# ArbPwrBoost_P7.net
KiCad netlist of a schematic drawn in Altium Designer
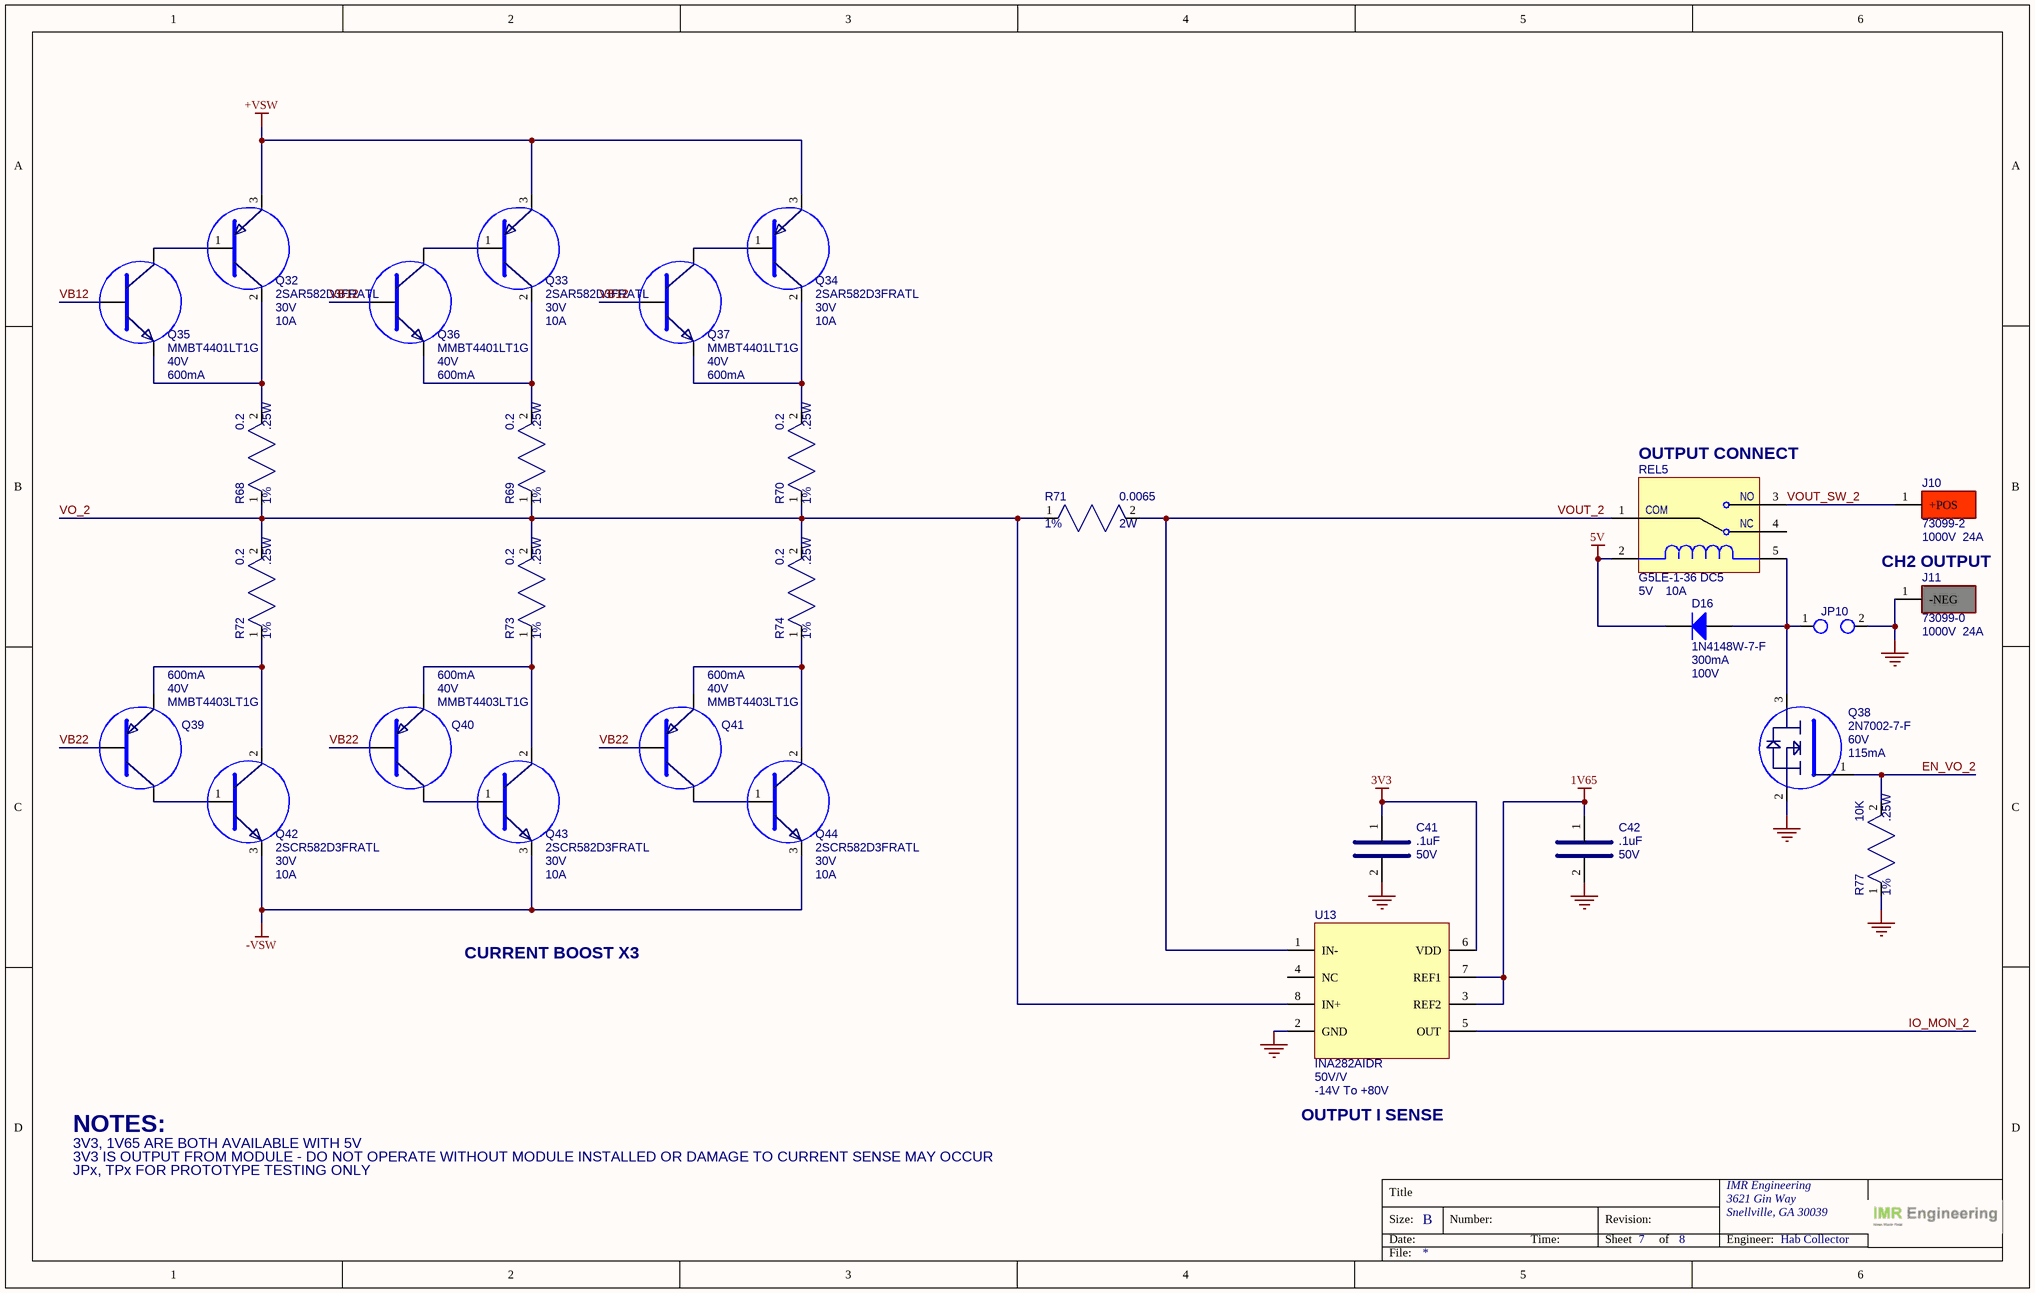
[diagram p0: ArbPwrBoost_P7.SchDoc]

(export (version "E")
  (design (tool "Eeschema 10.0.6"))
  (components
    (comp (ref "C41")
      (value ".1uF")
      (footprint "CAP_0805")
      (description "CAP CER 0.1UF 50V X7R 0805")
      (fields
        (field (name "MFG") "KYOCERA AVX")
        (field (name "VOLTAGE") "50V")
        (field (name "Comment") "KGM21NR71H104KT")
      )
      (libsource (lib "IMR_LIB_SCH_R2") (part "CAP_SMD_0.1UF_50V_0805"))
    )
    (comp (ref "C42")
      (value ".1uF")
      (footprint "CAP_0805")
      (description "CAP CER 0.1UF 50V X7R 0805")
      (fields
        (field (name "MFG") "KYOCERA AVX")
        (field (name "VOLTAGE") "50V")
        (field (name "Comment") "KGM21NR71H104KT")
      )
      (libsource (lib "IMR_LIB_SCH_R2") (part "CAP_SMD_0.1UF_50V_0805"))
    )
    (comp (ref "D16")
      (value "100V")
      (footprint "SOD123")
      (description "RELAY REED SPDT 250MA 5V")
      (fields
        (field (name "MFG") "Diodes Inc")
        (field (name "MFG_PN") "1N4148W-7-F")
        (field (name "CURRENT") "300mA")
        (field (name "Comment") "1N4148W-7-F")
      )
      (libsource (lib "IMR_LIB_SCH_R2") (part "DIODE_1N4148W-7-F"))
    )
    (comp (ref "J10")
      (value "1000V")
      (footprint "Pomona_73099-2")
      (description "CONN 4mm Banana Socket Right Angle PCB RED")
      (fields
        (field (name "MFG") "Pomona")
        (field (name "MFG_PN") "73099-2")
        (field (name "CURRENT") "24A")
        (field (name "Comment") "73099-2")
      )
      (libsource (lib "IMR_LIB_SCH_R2") (part "CONN_PANOMA_73099-2"))
    )
    (comp (ref "J11")
      (value "1000V")
      (footprint "Pomona_73099-0")
      (description "CONN 4mm Banana Socket Right Angle PCB BLK")
      (fields
        (field (name "MFG") "Pomona")
        (field (name "MFG_PN") "73099-0")
        (field (name "CURRENT") "24A")
        (field (name "Comment") "73099-0")
      )
      (libsource (lib "IMR_LIB_SCH_R2") (part "CONN_PANOMA_73099-0"))
    )
    (comp (ref "JP10")
      (value "PREC002SFAN-RC")
      (footprint "HDR_1X2_100MILL")
      (description "CONN HEADER VERT 2POS 2.54MM")
      (fields (field (name "MFG") "Sullins Connector Solutions"))
      (libsource (lib "IMR_LIB_SCH_R2") (part "CONN_JUMPER_2P_100MIL_VERT"))
    )
    (comp (ref "Q32")
      (value "30V")
      (footprint "TO-252")
      (description "TRANS PNP 30V 5.7A TO-252")
      (fields
        (field (name "MFG") "Rohm Semiconductor")
        (field (name "MFG_PN") "2SAR582D3FRATL")
        (field (name "CURRENT") "10A")
        (field (name "Comment") "2SAR582D3FRATL")
      )
      (libsource (lib "IMR_LIB_SCH_R2") (part "BJT_PNP_2SAR582D3FRATL"))
    )
    (comp (ref "Q33")
      (value "30V")
      (footprint "TO-252")
      (description "TRANS PNP 30V 5.7A TO-252")
      (fields
        (field (name "MFG") "Rohm Semiconductor")
        (field (name "MFG_PN") "2SAR582D3FRATL")
        (field (name "CURRENT") "10A")
        (field (name "Comment") "2SAR582D3FRATL")
      )
      (libsource (lib "IMR_LIB_SCH_R2") (part "BJT_PNP_2SAR582D3FRATL"))
    )
    (comp (ref "Q34")
      (value "30V")
      (footprint "TO-252")
      (description "TRANS PNP 30V 5.7A TO-252")
      (fields
        (field (name "MFG") "Rohm Semiconductor")
        (field (name "MFG_PN") "2SAR582D3FRATL")
        (field (name "CURRENT") "10A")
        (field (name "Comment") "2SAR582D3FRATL")
      )
      (libsource (lib "IMR_LIB_SCH_R2") (part "BJT_PNP_2SAR582D3FRATL"))
    )
    (comp (ref "Q35")
      (value "40V")
      (footprint "SOT-23")
      (description "TRANS NPN 40V 0.6A SOT23-3")
      (fields
        (field (name "MFG") "On Semiconductor")
        (field (name "MFG_PN") "MMBT4401LT1G")
        (field (name "CURRENT") "600mA")
        (field (name "Comment") "MMBT4401LT1G")
      )
      (libsource (lib "IMR_LIB_SCH_R2") (part "BJT_NPN_MMBT4401LT1G"))
    )
    (comp (ref "Q36")
      (value "40V")
      (footprint "SOT-23")
      (description "TRANS NPN 40V 0.6A SOT23-3")
      (fields
        (field (name "MFG") "On Semiconductor")
        (field (name "MFG_PN") "MMBT4401LT1G")
        (field (name "CURRENT") "600mA")
        (field (name "Comment") "MMBT4401LT1G")
      )
      (libsource (lib "IMR_LIB_SCH_R2") (part "BJT_NPN_MMBT4401LT1G"))
    )
    (comp (ref "Q37")
      (value "40V")
      (footprint "SOT-23")
      (description "TRANS NPN 40V 0.6A SOT23-3")
      (fields
        (field (name "MFG") "On Semiconductor")
        (field (name "MFG_PN") "MMBT4401LT1G")
        (field (name "CURRENT") "600mA")
        (field (name "Comment") "MMBT4401LT1G")
      )
      (libsource (lib "IMR_LIB_SCH_R2") (part "BJT_NPN_MMBT4401LT1G"))
    )
    (comp (ref "Q38")
      (value "60V")
      (footprint "SOT-23")
      (description "MOSFET N-CH 60V 115MA SOT23-3")
      (fields
        (field (name "MFG") "Diodes Inc")
        (field (name "MFG_PN") "2N7002-7-F")
        (field (name "CURRENT") "115mA")
        (field (name "Comment") "2N7002-7-F")
      )
      (libsource (lib "IMR_LIB_SCH_R2") (part "MOSFET_NCH_2N7002-7-F"))
    )
    (comp (ref "Q39")
      (value "40V")
      (footprint "SOT-23")
      (description "TRANS PNP 40V 0.6A SOT23-3")
      (fields
        (field (name "MFG") "On Semiconductor")
        (field (name "MFG_PN") "MMBT4403LT1G")
        (field (name "CURRENT") "600mA")
        (field (name "Comment") "MMBT4403LT1G")
      )
      (libsource (lib "IMR_LIB_SCH_R2") (part "BJT_PNP_MMBT4403LT1G"))
    )
    (comp (ref "Q40")
      (value "40V")
      (footprint "SOT-23")
      (description "TRANS PNP 40V 0.6A SOT23-3")
      (fields
        (field (name "MFG") "On Semiconductor")
        (field (name "MFG_PN") "MMBT4403LT1G")
        (field (name "CURRENT") "600mA")
        (field (name "Comment") "MMBT4403LT1G")
      )
      (libsource (lib "IMR_LIB_SCH_R2") (part "BJT_PNP_MMBT4403LT1G"))
    )
    (comp (ref "Q41")
      (value "40V")
      (footprint "SOT-23")
      (description "TRANS PNP 40V 0.6A SOT23-3")
      (fields
        (field (name "MFG") "On Semiconductor")
        (field (name "MFG_PN") "MMBT4403LT1G")
        (field (name "CURRENT") "600mA")
        (field (name "Comment") "MMBT4403LT1G")
      )
      (libsource (lib "IMR_LIB_SCH_R2") (part "BJT_PNP_MMBT4403LT1G"))
    )
    (comp (ref "Q42")
      (value "30V")
      (footprint "TO-252")
      (description "TRANS NPN 30V 10A TO-252")
      (fields
        (field (name "MFG") "Rohm Semiconductor")
        (field (name "MFG_PN") "2SCR582D3FRATL")
        (field (name "CURRENT") "10A")
        (field (name "Comment") "2SCR582D3FRATL")
      )
      (libsource (lib "IMR_LIB_SCH_R2") (part "BJT_NPN_2SCR582D3FRATL"))
    )
    (comp (ref "Q43")
      (value "30V")
      (footprint "TO-252")
      (description "TRANS NPN 30V 10A TO-252")
      (fields
        (field (name "MFG") "Rohm Semiconductor")
        (field (name "MFG_PN") "2SCR582D3FRATL")
        (field (name "CURRENT") "10A")
        (field (name "Comment") "2SCR582D3FRATL")
      )
      (libsource (lib "IMR_LIB_SCH_R2") (part "BJT_NPN_2SCR582D3FRATL"))
    )
    (comp (ref "Q44")
      (value "30V")
      (footprint "TO-252")
      (description "TRANS NPN 30V 10A TO-252")
      (fields
        (field (name "MFG") "Rohm Semiconductor")
        (field (name "MFG_PN") "2SCR582D3FRATL")
        (field (name "CURRENT") "10A")
        (field (name "Comment") "2SCR582D3FRATL")
      )
      (libsource (lib "IMR_LIB_SCH_R2") (part "BJT_NPN_2SCR582D3FRATL"))
    )
    (comp (ref "R68")
      (value "0.2")
      (footprint "RES_1206")
      (description "RES SMD 0.2 OHM 1% 1/4W 1206")
      (fields
        (field (name "MFG") "Yageo")
        (field (name "POWER") ".25W")
        (field (name "TOLERANCE") "1%")
        (field (name "Comment") "RL1206FR-070R2L")
      )
      (libsource (lib "IMR_LIB_SCH_R2") (part "RES_SMD_0.2_1206_1/4W_1%"))
    )
    (comp (ref "R69")
      (value "0.2")
      (footprint "RES_1206")
      (description "RES SMD 0.2 OHM 1% 1/4W 1206")
      (fields
        (field (name "MFG") "Yageo")
        (field (name "POWER") ".25W")
        (field (name "TOLERANCE") "1%")
        (field (name "Comment") "RL1206FR-070R2L")
      )
      (libsource (lib "IMR_LIB_SCH_R2") (part "RES_SMD_0.2_1206_1/4W_1%"))
    )
    (comp (ref "R70")
      (value "0.2")
      (footprint "RES_1206")
      (description "RES SMD 0.2 OHM 1% 1/4W 1206")
      (fields
        (field (name "MFG") "Yageo")
        (field (name "POWER") ".25W")
        (field (name "TOLERANCE") "1%")
        (field (name "Comment") "RL1206FR-070R2L")
      )
      (libsource (lib "IMR_LIB_SCH_R2") (part "RES_SMD_0.2_1206_1/4W_1%"))
    )
    (comp (ref "R71")
      (value "0.0065")
      (footprint "RES_2512")
      (description "RES SMD 0.0065 OHM 1% 2W 2512")
      (fields
        (field (name "MFG") "Vishay Dale")
        (field (name "TOLERANCE") "1%")
        (field (name "POWER") "2W")
        (field (name "Comment") "WSL25126L500FEA18")
      )
      (libsource (lib "IMR_LIB_SCH_R2") (part "RES_SMD_0.0065_2512_2W_1%"))
    )
    (comp (ref "R72")
      (value "0.2")
      (footprint "RES_1206")
      (description "RES SMD 0.2 OHM 1% 1/4W 1206")
      (fields
        (field (name "MFG") "Yageo")
        (field (name "POWER") ".25W")
        (field (name "TOLERANCE") "1%")
        (field (name "Comment") "RL1206FR-070R2L")
      )
      (libsource (lib "IMR_LIB_SCH_R2") (part "RES_SMD_0.2_1206_1/4W_1%"))
    )
    (comp (ref "R73")
      (value "0.2")
      (footprint "RES_1206")
      (description "RES SMD 0.2 OHM 1% 1/4W 1206")
      (fields
        (field (name "MFG") "Yageo")
        (field (name "POWER") ".25W")
        (field (name "TOLERANCE") "1%")
        (field (name "Comment") "RL1206FR-070R2L")
      )
      (libsource (lib "IMR_LIB_SCH_R2") (part "RES_SMD_0.2_1206_1/4W_1%"))
    )
    (comp (ref "R74")
      (value "0.2")
      (footprint "RES_1206")
      (description "RES SMD 0.2 OHM 1% 1/4W 1206")
      (fields
        (field (name "MFG") "Yageo")
        (field (name "POWER") ".25W")
        (field (name "TOLERANCE") "1%")
        (field (name "Comment") "RL1206FR-070R2L")
      )
      (libsource (lib "IMR_LIB_SCH_R2") (part "RES_SMD_0.2_1206_1/4W_1%"))
    )
    (comp (ref "R77")
      (value "10K")
      (footprint "RES_0805")
      (description "RES SMD 10K OHM 1% 1/4W 0805")
      (fields
        (field (name "MFG") "Yageo")
        (field (name "POWER") ".25W")
        (field (name "TOLERANCE") "1%")
        (field (name "Comment") "RC0805FR-7W10KL")
      )
      (libsource (lib "IMR_LIB_SCH_R2") (part "RES_SMD_10K_0805_1/4W_1%"))
    )
    (comp (ref "REL5")
      (value "5V")
      (footprint "G5LE")
      (description "RELAY GEN PURPOSE SPDT 10A 5V")
      (fields
        (field (name "MFG") "Omron")
        (field (name "MFG_PN") "G5LE-1-36 DC5")
        (field (name "CURRENT") "10A")
        (field (name "Comment") "G5LE-1-36 DC5")
      )
      (libsource (lib "IMR_LIB_SCH_R2") (part "RELAY_G5LE-1-36 DC5"))
    )
    (comp (ref "U13")
      (value "50V/V")
      (footprint "SOIC-8_54")
      (description "IC CURRENT SENSE 0.4% 50V/V SOIC-8")
      (fields
        (field (name "MFG") "Texas Instruments")
        (field (name "COMMON MODE") "-14V To +80V")
        (field (name "MFG_PN") "INA282AIDR")
        (field (name "Comment") "INA282AIDR")
      )
      (libsource (lib "IMR_LIB_SCH_R2") (part "IC_INA282AIDR"))
    )
  )
  (nets
    (net (code "1") (name "+VSW") (class "Default")
      (node (ref "Q32") (pin "3") (pinfunction "E_3") (pintype "passive"))
      (node (ref "Q33") (pin "3") (pinfunction "E_3") (pintype "passive"))
      (node (ref "Q34") (pin "3") (pinfunction "E_3") (pintype "passive"))
    )
    (net (code "2") (name "-VSW") (class "Default")
      (node (ref "Q42") (pin "3") (pinfunction "E_3") (pintype "passive"))
      (node (ref "Q43") (pin "3") (pinfunction "E_3") (pintype "passive"))
      (node (ref "Q44") (pin "3") (pinfunction "E_3") (pintype "passive"))
    )
    (net (code "3") (name "/EN_VO_2") (class "Default")
      (node (ref "Q38") (pin "1") (pinfunction "B_1") (pintype "passive"))
      (node (ref "R77") (pin "2") (pinfunction "2_2") (pintype "passive"))
    )
    (net (code "4") (name "/IO_MON_2") (class "Default")
      (node (ref "U13") (pin "5") (pinfunction "OUT_5") (pintype "passive"))
    )
    (net (code "5") (name "/VB12") (class "Default")
      (node (ref "Q35") (pin "1") (pinfunction "B_1") (pintype "passive"))
      (node (ref "Q36") (pin "1") (pinfunction "B_1") (pintype "passive"))
      (node (ref "Q37") (pin "1") (pinfunction "B_1") (pintype "passive"))
    )
    (net (code "6") (name "/VB22") (class "Default")
      (node (ref "Q39") (pin "1") (pinfunction "B_1") (pintype "passive"))
      (node (ref "Q40") (pin "1") (pinfunction "B_1") (pintype "passive"))
      (node (ref "Q41") (pin "1") (pinfunction "B_1") (pintype "passive"))
    )
    (net (code "7") (name "/VOUT_2") (class "Default")
      (node (ref "R71") (pin "2") (pinfunction "2_2") (pintype "passive"))
      (node (ref "REL5") (pin "1") (pinfunction "COM_1") (pintype "passive"))
      (node (ref "U13") (pin "1") (pinfunction "IN-_1") (pintype "passive"))
    )
    (net (code "8") (name "/VOUT_SW_2") (class "Default")
      (node (ref "J10") (pin "1") (pinfunction "+POS_1") (pintype "passive"))
      (node (ref "REL5") (pin "3") (pinfunction "NO_3") (pintype "passive"))
    )
    (net (code "9") (name "/VO_2") (class "Default")
      (node (ref "R68") (pin "1") (pinfunction "1_1") (pintype "passive"))
      (node (ref "R69") (pin "1") (pinfunction "1_1") (pintype "passive"))
      (node (ref "R70") (pin "1") (pinfunction "1_1") (pintype "passive"))
      (node (ref "R71") (pin "1") (pinfunction "1_1") (pintype "passive"))
      (node (ref "R72") (pin "2") (pinfunction "2_2") (pintype "passive"))
      (node (ref "R73") (pin "2") (pinfunction "2_2") (pintype "passive"))
      (node (ref "R74") (pin "2") (pinfunction "2_2") (pintype "passive"))
      (node (ref "U13") (pin "8") (pinfunction "IN+_8") (pintype "passive"))
    )
    (net (code "10") (name "1V65") (class "Default")
      (node (ref "C42") (pin "1") (pinfunction "1_1") (pintype "passive"))
      (node (ref "U13") (pin "3") (pinfunction "REF2_3") (pintype "passive"))
      (node (ref "U13") (pin "7") (pinfunction "REF1_7") (pintype "passive"))
    )
    (net (code "11") (name "3V3") (class "Default")
      (node (ref "C41") (pin "1") (pinfunction "1_1") (pintype "passive"))
      (node (ref "U13") (pin "6") (pinfunction "VDD_6") (pintype "passive"))
    )
    (net (code "12") (name "5V") (class "Default")
      (node (ref "D16") (pin "2") (pinfunction "K_2") (pintype "passive"))
      (node (ref "REL5") (pin "2") (pintype "passive"))
    )
    (net (code "13") (name "GND") (class "Default")
      (node (ref "C41") (pin "2") (pinfunction "2_2") (pintype "passive"))
      (node (ref "C42") (pin "2") (pinfunction "2_2") (pintype "passive"))
      (node (ref "J11") (pin "1") (pinfunction "-NEG_1") (pintype "passive"))
      (node (ref "JP10") (pin "2") (pintype "passive"))
      (node (ref "Q38") (pin "2") (pinfunction "E_2") (pintype "passive"))
      (node (ref "R77") (pin "1") (pinfunction "1_1") (pintype "passive"))
      (node (ref "U13") (pin "2") (pinfunction "GND_2") (pintype "passive"))
    )
    (net (code "14") (name "Net-(D16-A)") (class "Default")
      (node (ref "D16") (pin "1") (pinfunction "A_1") (pintype "passive"))
      (node (ref "JP10") (pin "1") (pintype "passive"))
      (node (ref "Q38") (pin "3") (pinfunction "C_3") (pintype "passive"))
      (node (ref "REL5") (pin "5") (pintype "passive"))
    )
    (net (code "15") (name "Net-(Q32-B)") (class "Default")
      (node (ref "Q32") (pin "1") (pinfunction "B_1") (pintype "passive"))
      (node (ref "Q35") (pin "3") (pinfunction "C_3") (pintype "passive"))
    )
    (net (code "16") (name "Net-(Q32-C)") (class "Default")
      (node (ref "Q32") (pin "2") (pinfunction "C_2") (pintype "passive"))
      (node (ref "Q35") (pin "2") (pinfunction "E_2") (pintype "passive"))
      (node (ref "R68") (pin "2") (pinfunction "2_2") (pintype "passive"))
    )
    (net (code "17") (name "Net-(Q33-B)") (class "Default")
      (node (ref "Q33") (pin "1") (pinfunction "B_1") (pintype "passive"))
      (node (ref "Q36") (pin "3") (pinfunction "C_3") (pintype "passive"))
    )
    (net (code "18") (name "Net-(Q33-C)") (class "Default")
      (node (ref "Q33") (pin "2") (pinfunction "C_2") (pintype "passive"))
      (node (ref "Q36") (pin "2") (pinfunction "E_2") (pintype "passive"))
      (node (ref "R69") (pin "2") (pinfunction "2_2") (pintype "passive"))
    )
    (net (code "19") (name "Net-(Q34-B)") (class "Default")
      (node (ref "Q34") (pin "1") (pinfunction "B_1") (pintype "passive"))
      (node (ref "Q37") (pin "3") (pinfunction "C_3") (pintype "passive"))
    )
    (net (code "20") (name "Net-(Q34-C)") (class "Default")
      (node (ref "Q34") (pin "2") (pinfunction "C_2") (pintype "passive"))
      (node (ref "Q37") (pin "2") (pinfunction "E_2") (pintype "passive"))
      (node (ref "R70") (pin "2") (pinfunction "2_2") (pintype "passive"))
    )
    (net (code "21") (name "Net-(Q39-C)") (class "Default")
      (node (ref "Q39") (pin "3") (pinfunction "C_3") (pintype "passive"))
      (node (ref "Q42") (pin "1") (pinfunction "B_1") (pintype "passive"))
    )
    (net (code "22") (name "Net-(Q39-E)") (class "Default")
      (node (ref "Q39") (pin "2") (pinfunction "E_2") (pintype "passive"))
      (node (ref "Q42") (pin "2") (pinfunction "C_2") (pintype "passive"))
      (node (ref "R72") (pin "1") (pinfunction "1_1") (pintype "passive"))
    )
    (net (code "23") (name "Net-(Q40-C)") (class "Default")
      (node (ref "Q40") (pin "3") (pinfunction "C_3") (pintype "passive"))
      (node (ref "Q43") (pin "1") (pinfunction "B_1") (pintype "passive"))
    )
    (net (code "24") (name "Net-(Q40-E)") (class "Default")
      (node (ref "Q40") (pin "2") (pinfunction "E_2") (pintype "passive"))
      (node (ref "Q43") (pin "2") (pinfunction "C_2") (pintype "passive"))
      (node (ref "R73") (pin "1") (pinfunction "1_1") (pintype "passive"))
    )
    (net (code "25") (name "Net-(Q41-C)") (class "Default")
      (node (ref "Q41") (pin "3") (pinfunction "C_3") (pintype "passive"))
      (node (ref "Q44") (pin "1") (pinfunction "B_1") (pintype "passive"))
    )
    (net (code "26") (name "Net-(Q41-E)") (class "Default")
      (node (ref "Q41") (pin "2") (pinfunction "E_2") (pintype "passive"))
      (node (ref "Q44") (pin "2") (pinfunction "C_2") (pintype "passive"))
      (node (ref "R74") (pin "1") (pinfunction "1_1") (pintype "passive"))
    )
    (net (code "27") (name "unconnected-(REL5-NC-Pad4)") (class "Default")
      (node (ref "REL5") (pin "4") (pinfunction "NC_4") (pintype "passive"))
    )
    (net (code "28") (name "unconnected-(U13-NC-Pad4)") (class "Default")
      (node (ref "U13") (pin "4") (pinfunction "NC_4") (pintype "passive"))
    )
  )
)
